# e3_tp1_ej1.net
KiCad netlist of a schematic drawn in Altium Designer
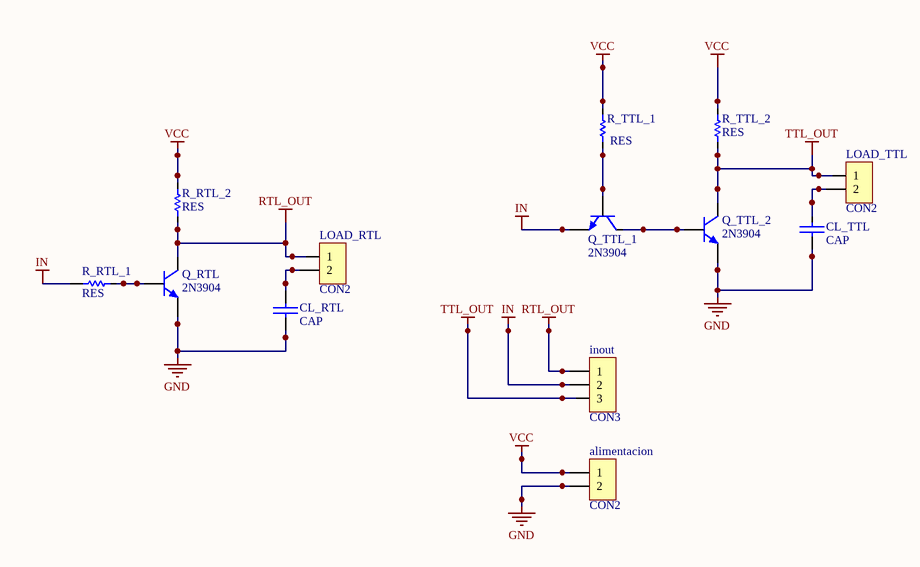
[diagram p0: e3_tp1_ej1.SchDoc]

(export (version "E")
  (design (tool "Eeschema 10.0.6"))
  (components
    (comp (ref "alimentacion") (value "CON2") (footprint "SIP2") (libsource (lib "LIBEBAL") (part "CON2")))
    (comp (ref "CL_RTL") (value "CAP") (footprint "CAP200") (libsource (lib "LIBEBAL") (part "CAP")))
    (comp (ref "CL_TTL") (value "CAP") (footprint "CAP200") (libsource (lib "LIBEBAL") (part "CAP")))
    (comp (ref "inout") (value "CON3") (footprint "SIP3") (libsource (lib "LIBEBAL") (part "CON3")))
    (comp (ref "LOAD_RTL") (value "CON2") (footprint "SIP2") (libsource (lib "LIBEBAL") (part "CON2")))
    (comp (ref "LOAD_TTL") (value "CON2") (footprint "SIP2") (libsource (lib "LIBEBAL") (part "CON2")))
    (comp (ref "Q_RTL")
      (value "2N3904")
      (footprint "TO-92A")
      (description "NPN General Purpose Amplifier")
      (fields (field (name "PUBLISHER") "Altium Limited"))
      (libsource (lib "Miscellaneous Devices") (part "2N3904"))
    )
    (comp (ref "Q_TTL_1")
      (value "2N3904")
      (footprint "TO-92A")
      (description "NPN General Purpose Amplifier")
      (fields (field (name "PUBLISHER") "Altium Limited"))
      (libsource (lib "Miscellaneous Devices") (part "2N3904"))
    )
    (comp (ref "Q_TTL_2")
      (value "2N3904")
      (footprint "TO-92A")
      (description "NPN General Purpose Amplifier")
      (fields (field (name "PUBLISHER") "Altium Limited"))
      (libsource (lib "Miscellaneous Devices") (part "2N3904"))
    )
    (comp (ref "R_RTL_1") (value "RES") (footprint "RES300") (libsource (lib "LIBEBAL") (part "RES")))
    (comp (ref "R_RTL_2") (value "RES") (footprint "RES300") (libsource (lib "LIBEBAL") (part "RES")))
    (comp (ref "R_TTL_1") (value "RES") (footprint "RES300") (libsource (lib "LIBEBAL") (part "RES")))
    (comp (ref "R_TTL_2") (value "RES") (footprint "RES300") (libsource (lib "LIBEBAL") (part "RES")))
  )
  (nets
    (net (code "1") (name "GND") (class "Default")
      (node (ref "CL_RTL") (pin "2") (pinfunction "2_2") (pintype "passive"))
      (node (ref "CL_TTL") (pin "2") (pinfunction "2_2") (pintype "passive"))
      (node (ref "Q_RTL") (pin "1") (pinfunction "E_1") (pintype "passive"))
      (node (ref "Q_TTL_2") (pin "1") (pinfunction "E_1") (pintype "passive"))
      (node (ref "alimentacion") (pin "2") (pinfunction "2_2") (pintype "passive"))
    )
    (net (code "2") (name "IN") (class "Default")
      (node (ref "Q_TTL_1") (pin "1") (pinfunction "E_1") (pintype "passive"))
      (node (ref "R_RTL_1") (pin "1") (pinfunction "1_1") (pintype "passive"))
      (node (ref "inout") (pin "2") (pinfunction "2_2") (pintype "passive"))
    )
    (net (code "3") (name "Net-(CL_RTL-Pad1)") (class "Default")
      (node (ref "CL_RTL") (pin "1") (pinfunction "1_1") (pintype "passive"))
      (node (ref "LOAD_RTL") (pin "2") (pinfunction "2_2") (pintype "passive"))
    )
    (net (code "4") (name "Net-(CL_TTL-Pad1)") (class "Default")
      (node (ref "CL_TTL") (pin "1") (pinfunction "1_1") (pintype "passive"))
      (node (ref "LOAD_TTL") (pin "2") (pinfunction "2_2") (pintype "passive"))
    )
    (net (code "5") (name "Net-(Q_RTL-B)") (class "Default")
      (node (ref "Q_RTL") (pin "2") (pinfunction "B_2") (pintype "passive"))
      (node (ref "R_RTL_1") (pin "2") (pinfunction "2_2") (pintype "passive"))
    )
    (net (code "6") (name "Net-(Q_TTL_1-B)") (class "Default")
      (node (ref "Q_TTL_1") (pin "2") (pinfunction "B_2") (pintype "passive"))
      (node (ref "R_TTL_1") (pin "1") (pinfunction "1_1") (pintype "passive"))
    )
    (net (code "7") (name "Net-(Q_TTL_1-C)") (class "Default")
      (node (ref "Q_TTL_1") (pin "3") (pinfunction "C_3") (pintype "passive"))
      (node (ref "Q_TTL_2") (pin "2") (pinfunction "B_2") (pintype "passive"))
    )
    (net (code "8") (name "RTL_OUT") (class "Default")
      (node (ref "LOAD_RTL") (pin "1") (pinfunction "1_1") (pintype "passive"))
      (node (ref "Q_RTL") (pin "3") (pinfunction "C_3") (pintype "passive"))
      (node (ref "R_RTL_2") (pin "1") (pinfunction "1_1") (pintype "passive"))
      (node (ref "inout") (pin "1") (pinfunction "1_1") (pintype "passive"))
    )
    (net (code "9") (name "TTL_OUT") (class "Default")
      (node (ref "LOAD_TTL") (pin "1") (pinfunction "1_1") (pintype "passive"))
      (node (ref "Q_TTL_2") (pin "3") (pinfunction "C_3") (pintype "passive"))
      (node (ref "R_TTL_2") (pin "1") (pinfunction "1_1") (pintype "passive"))
      (node (ref "inout") (pin "3") (pinfunction "3_3") (pintype "passive"))
    )
    (net (code "10") (name "VCC") (class "Default")
      (node (ref "R_RTL_2") (pin "2") (pinfunction "2_2") (pintype "passive"))
      (node (ref "R_TTL_1") (pin "2") (pinfunction "2_2") (pintype "passive"))
      (node (ref "R_TTL_2") (pin "2") (pinfunction "2_2") (pintype "passive"))
      (node (ref "alimentacion") (pin "1") (pinfunction "1_1") (pintype "passive"))
    )
  )
)
